# Board.net
KiCad netlist of a schematic drawn in Altium Designer
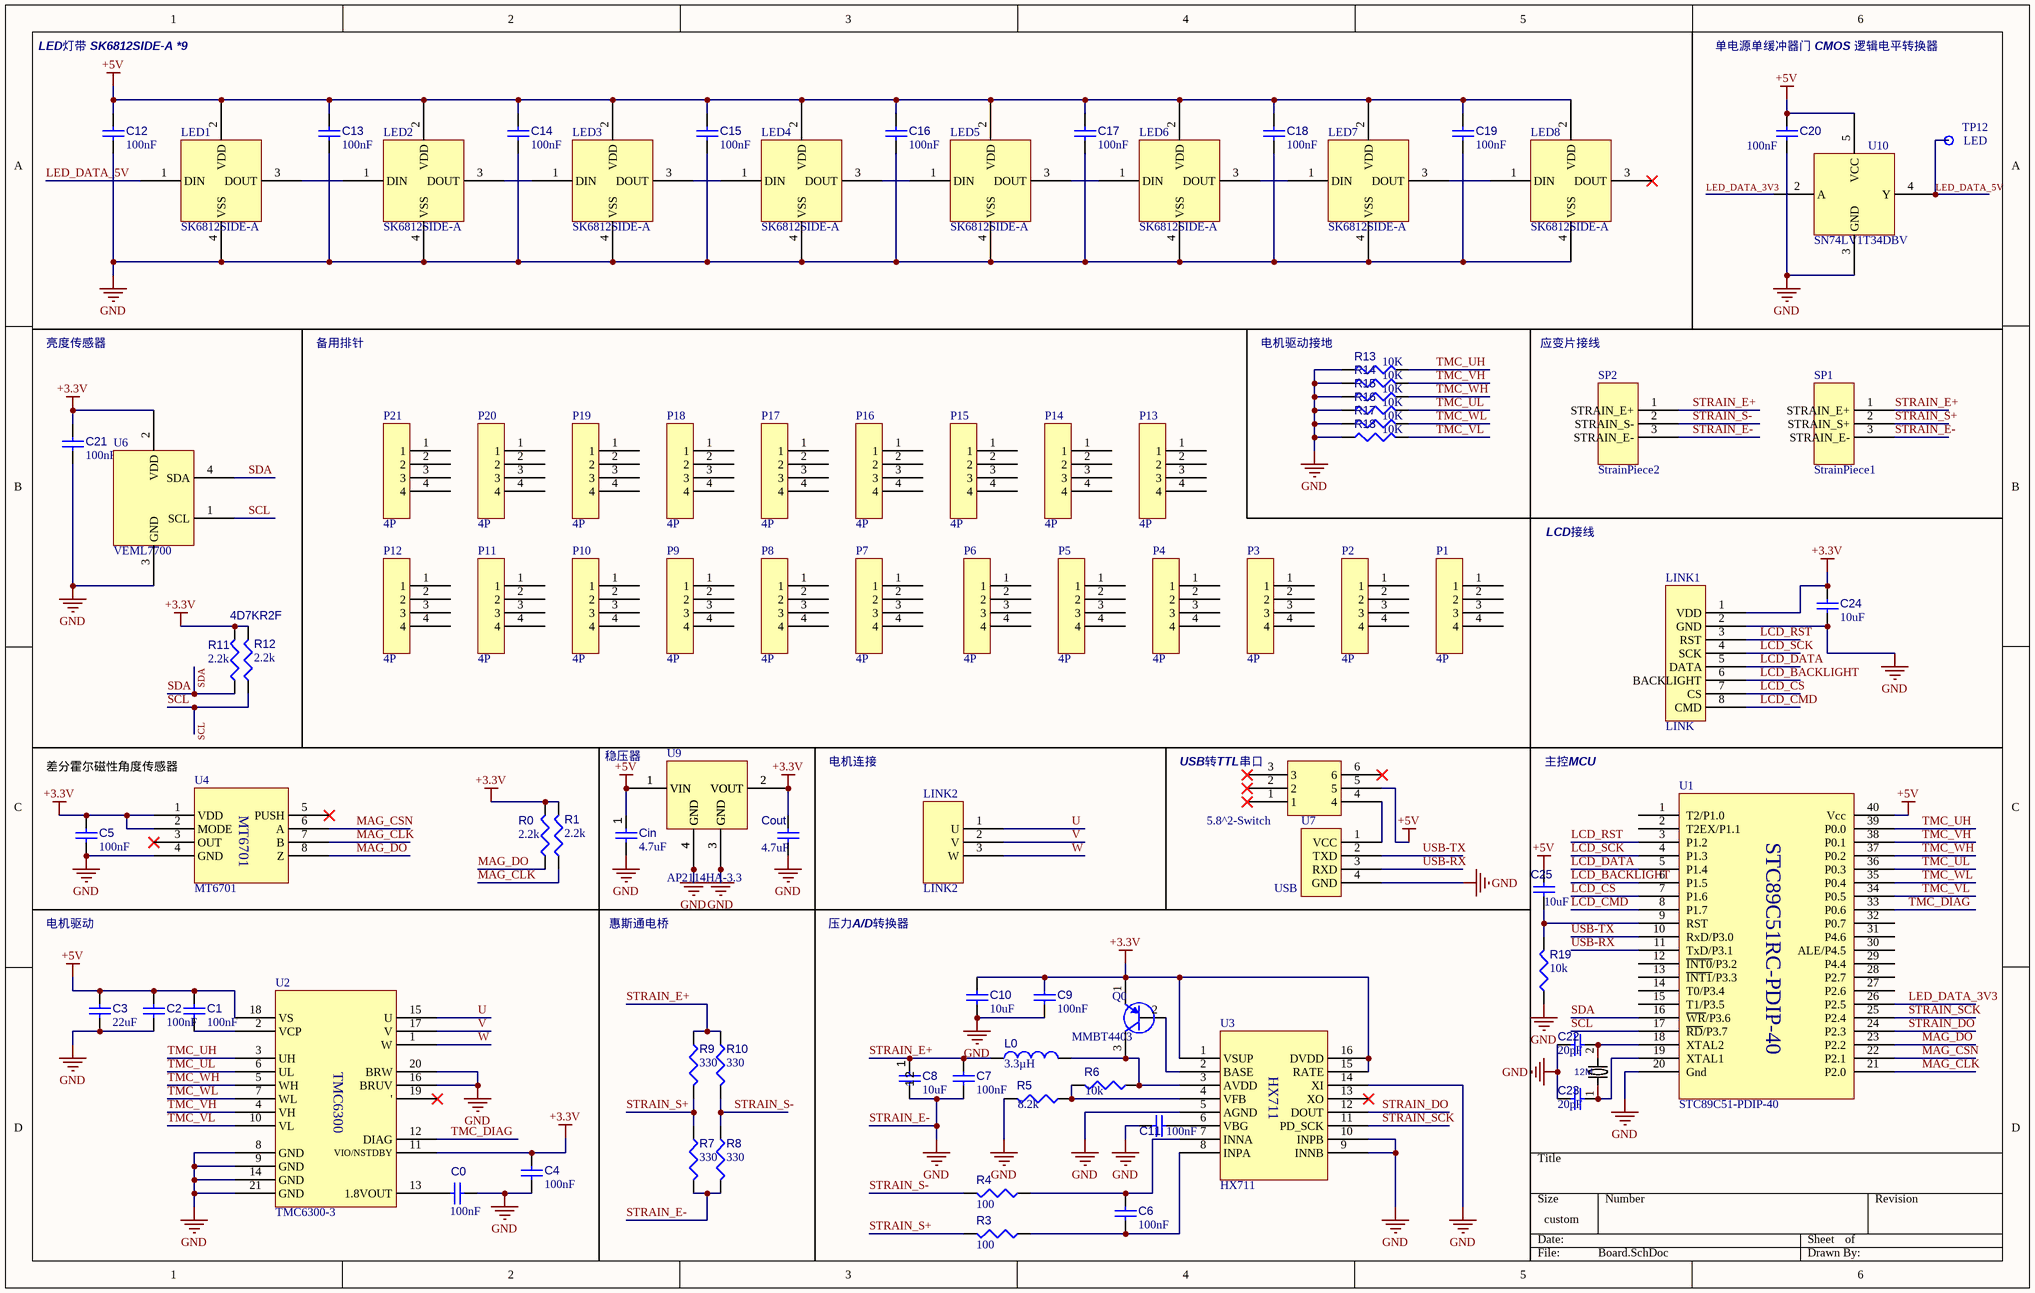
[diagram p0: Board.SchDoc]

(export (version "E")
  (design (tool "Eeschema 10.0.6"))
  (components
    (comp (ref "C0")
      (value "100nF")
      (footprint "0805贴片电容")
      (description "Chip Capacitor, 0.1 uF, +/- 5%, 16 V, 0402 (1005 Metric)")
      (fields (field (name "TOLERANCE") "5%") (field (name "Comment") "Capacitor 0.1 uF +/- 5% 16 V 0402"))
      (libsource (lib "IC") (part "CAP-NP-2"))
    )
    (comp (ref "C1")
      (value "100nF")
      (footprint "0805贴片电容")
      (description "Chip Capacitor, 0.1 uF, +/- 5%, 16 V, 0402 (1005 Metric)")
      (fields (field (name "TOLERANCE") "5%") (field (name "Comment") "Capacitor 0.1 uF +/- 5% 16 V 0402"))
      (libsource (lib "IC") (part "CAP-NP-2"))
    )
    (comp (ref "C2")
      (value "100nF")
      (footprint "0805贴片电容")
      (description "Chip Capacitor, 0.1 uF, +/- 5%, 16 V, 0402 (1005 Metric)")
      (fields (field (name "TOLERANCE") "5%") (field (name "Comment") "Capacitor 0.1 uF +/- 5% 16 V 0402"))
      (libsource (lib "IC") (part "CAP-NP-2"))
    )
    (comp (ref "C3")
      (value "22uF")
      (footprint "0805贴片电容")
      (description "Chip Capacitor, 0.1 uF, +/- 5%, 16 V, 0402 (1005 Metric)")
      (fields (field (name "TOLERANCE") "5%") (field (name "Comment") "Capacitor 0.1 uF +/- 5% 16 V 0402"))
      (libsource (lib "IC") (part "CAP-NP-2"))
    )
    (comp (ref "C4")
      (value "100nF")
      (footprint "0805贴片电容")
      (description "Chip Capacitor, 0.1 uF, +/- 5%, 16 V, 0402 (1005 Metric)")
      (fields (field (name "TOLERANCE") "5%") (field (name "Comment") "Capacitor 0.1 uF +/- 5% 16 V 0402"))
      (libsource (lib "IC") (part "CAP-NP-2"))
    )
    (comp (ref "C5")
      (value "100nF")
      (footprint "0805贴片电容")
      (description "Chip Capacitor, 0.1 uF, +/- 5%, 16 V, 0402 (1005 Metric)")
      (fields (field (name "TOLERANCE") "5%") (field (name "Comment") "Capacitor 0.1 uF +/- 5% 16 V 0402"))
      (libsource (lib "IC") (part "CAP-NP-2"))
    )
    (comp (ref "C6")
      (value "100nF")
      (footprint "0805贴片电容")
      (description "Chip Capacitor, 0.1 uF, +/- 5%, 16 V, 0402 (1005 Metric)")
      (fields (field (name "TOLERANCE") "5%") (field (name "Comment") "Capacitor 0.1 uF +/- 5% 16 V 0402"))
      (libsource (lib "IC") (part "CAP-NP-2"))
    )
    (comp (ref "C7")
      (value "100nF")
      (footprint "0805贴片电容")
      (description "Chip Capacitor, 0.1 uF, +/- 5%, 16 V, 0402 (1005 Metric)")
      (fields (field (name "TOLERANCE") "5%") (field (name "Comment") "Capacitor 0.1 uF +/- 5% 16 V 0402"))
      (libsource (lib "IC") (part "CAP-NP-2"))
    )
    (comp (ref "C8")
      (value "10uF")
      (footprint "0805贴片电容")
      (description "Chip Capacitor, 0.1 uF, +/- 5%, 16 V, 0402 (1005 Metric)")
      (fields (field (name "TOLERANCE") "5%") (field (name "Comment") "Capacitor 0.1 uF +/- 5% 16 V 0402"))
      (libsource (lib "") (part "CAP-NP-2_2"))
    )
    (comp (ref "C9")
      (value "100nF")
      (footprint "0805贴片电容")
      (description "Chip Capacitor, 0.1 uF, +/- 5%, 16 V, 0402 (1005 Metric)")
      (fields (field (name "TOLERANCE") "5%") (field (name "Comment") "Capacitor 0.1 uF +/- 5% 16 V 0402"))
      (libsource (lib "IC") (part "CAP-NP-2"))
    )
    (comp (ref "C10")
      (value "10uF")
      (footprint "0805贴片电容")
      (description "Chip Capacitor, 0.1 uF, +/- 5%, 16 V, 0402 (1005 Metric)")
      (fields (field (name "TOLERANCE") "5%") (field (name "Comment") "Capacitor 0.1 uF +/- 5% 16 V 0402"))
      (libsource (lib "IC") (part "CAP-NP-2"))
    )
    (comp (ref "C11")
      (value "100nF")
      (footprint "0805贴片电容")
      (description "Chip Capacitor, 0.1 uF, +/- 5%, 16 V, 0402 (1005 Metric)")
      (fields (field (name "TOLERANCE") "5%") (field (name "Comment") "Capacitor 0.1 uF +/- 5% 16 V 0402"))
      (libsource (lib "IC") (part "CAP-NP-2"))
    )
    (comp (ref "C12")
      (value "100nF")
      (footprint "0805贴片电容")
      (description "Chip Capacitor, 0.1 uF, +/- 5%, 16 V, 0402 (1005 Metric)")
      (fields (field (name "TOLERANCE") "5%") (field (name "Comment") "Capacitor 0.1 uF +/- 5% 16 V 0402"))
      (libsource (lib "IC") (part "CAP-NP-2"))
    )
    (comp (ref "C13")
      (value "100nF")
      (footprint "0805贴片电容")
      (description "Chip Capacitor, 0.1 uF, +/- 5%, 16 V, 0402 (1005 Metric)")
      (fields (field (name "TOLERANCE") "5%") (field (name "Comment") "Capacitor 0.1 uF +/- 5% 16 V 0402"))
      (libsource (lib "IC") (part "CAP-NP-2"))
    )
    (comp (ref "C14")
      (value "100nF")
      (footprint "0805贴片电容")
      (description "Chip Capacitor, 0.1 uF, +/- 5%, 16 V, 0402 (1005 Metric)")
      (fields (field (name "TOLERANCE") "5%") (field (name "Comment") "Capacitor 0.1 uF +/- 5% 16 V 0402"))
      (libsource (lib "IC") (part "CAP-NP-2"))
    )
    (comp (ref "C15")
      (value "100nF")
      (footprint "0805贴片电容")
      (description "Chip Capacitor, 0.1 uF, +/- 5%, 16 V, 0402 (1005 Metric)")
      (fields (field (name "TOLERANCE") "5%") (field (name "Comment") "Capacitor 0.1 uF +/- 5% 16 V 0402"))
      (libsource (lib "IC") (part "CAP-NP-2"))
    )
    (comp (ref "C16")
      (value "100nF")
      (footprint "0805贴片电容")
      (description "Chip Capacitor, 0.1 uF, +/- 5%, 16 V, 0402 (1005 Metric)")
      (fields (field (name "TOLERANCE") "5%") (field (name "Comment") "Capacitor 0.1 uF +/- 5% 16 V 0402"))
      (libsource (lib "IC") (part "CAP-NP-2"))
    )
    (comp (ref "C17")
      (value "100nF")
      (footprint "0805贴片电容")
      (description "Chip Capacitor, 0.1 uF, +/- 5%, 16 V, 0402 (1005 Metric)")
      (fields (field (name "TOLERANCE") "5%") (field (name "Comment") "Capacitor 0.1 uF +/- 5% 16 V 0402"))
      (libsource (lib "IC") (part "CAP-NP-2"))
    )
    (comp (ref "C18")
      (value "100nF")
      (footprint "0805贴片电容")
      (description "Chip Capacitor, 0.1 uF, +/- 5%, 16 V, 0402 (1005 Metric)")
      (fields (field (name "TOLERANCE") "5%") (field (name "Comment") "Capacitor 0.1 uF +/- 5% 16 V 0402"))
      (libsource (lib "IC") (part "CAP-NP-2"))
    )
    (comp (ref "C19")
      (value "100nF")
      (footprint "0805贴片电容")
      (description "Chip Capacitor, 0.1 uF, +/- 5%, 16 V, 0402 (1005 Metric)")
      (fields (field (name "TOLERANCE") "5%") (field (name "Comment") "Capacitor 0.1 uF +/- 5% 16 V 0402"))
      (libsource (lib "IC") (part "CAP-NP-2"))
    )
    (comp (ref "C20")
      (value "100nF")
      (footprint "0805贴片电容")
      (description "Chip Capacitor, 0.1 uF, +/- 5%, 16 V, 0402 (1005 Metric)")
      (fields (field (name "TOLERANCE") "5%") (field (name "Comment") "Capacitor 0.1 uF +/- 5% 16 V 0402"))
      (libsource (lib "IC") (part "CAP-NP-2"))
    )
    (comp (ref "C21")
      (value "100nF")
      (footprint "0805贴片电容")
      (description "Chip Capacitor, 0.1 uF, +/- 5%, 16 V, 0402 (1005 Metric)")
      (fields (field (name "TOLERANCE") "5%") (field (name "Comment") "Capacitor 0.1 uF +/- 5% 16 V 0402"))
      (libsource (lib "IC") (part "CAP-NP-2"))
    )
    (comp (ref "C22")
      (value "20pF")
      (footprint "0805贴片电容")
      (description "Chip Capacitor, 0.1 uF, +/- 5%, 16 V, 0402 (1005 Metric)")
      (fields (field (name "TOLERANCE") "5%") (field (name "Comment") "Capacitor 0.1 uF +/- 5% 16 V 0402"))
      (libsource (lib "IC") (part "CAP-NP-2"))
    )
    (comp (ref "C23")
      (value "20pF")
      (footprint "0805贴片电容")
      (description "Chip Capacitor, 0.1 uF, +/- 5%, 16 V, 0402 (1005 Metric)")
      (fields (field (name "TOLERANCE") "5%") (field (name "Comment") "Capacitor 0.1 uF +/- 5% 16 V 0402"))
      (libsource (lib "IC") (part "CAP-NP-2"))
    )
    (comp (ref "C24")
      (value "10uF")
      (footprint "0805贴片电容")
      (description "Chip Capacitor, 0.1 uF, +/- 5%, 16 V, 0402 (1005 Metric)")
      (fields (field (name "TOLERANCE") "5%") (field (name "Comment") "Capacitor 0.1 uF +/- 5% 16 V 0402"))
      (libsource (lib "IC") (part "CAP-NP-2"))
    )
    (comp (ref "C25")
      (value "10uF")
      (footprint "0805贴片电容")
      (description "Chip Capacitor, 0.1 uF, +/- 5%, 16 V, 0402 (1005 Metric)")
      (fields (field (name "TOLERANCE") "5%") (field (name "Comment") "Capacitor 0.1 uF +/- 5% 16 V 0402"))
      (libsource (lib "IC") (part "CAP-NP-2"))
    )
    (comp (ref "Cin")
      (value "4.7uF")
      (footprint "0805贴片电容")
      (description "Chip Capacitor, 0.1 uF, +/- 5%, 16 V, 0402 (1005 Metric)")
      (fields (field (name "TOLERANCE") "5%") (field (name "Comment") "Capacitor 0.1 uF +/- 5% 16 V 0402"))
      (libsource (lib "") (part "CAP-NP-2_1"))
    )
    (comp (ref "Cout")
      (value "4.7uF")
      (footprint "0805贴片电容")
      (description "Chip Capacitor, 0.1 uF, +/- 5%, 16 V, 0402 (1005 Metric)")
      (fields (field (name "TOLERANCE") "5%") (field (name "Comment") "Capacitor 0.1 uF +/- 5% 16 V 0402"))
      (libsource (lib "IC") (part "CAP-NP-2"))
    )
    (comp (ref "L0")
      (value "3.3µH")
      (footprint "0805贴片电容")
      (description "Chip Inductor, 1 uH, +/- 20%, 1 MHz, -55 to 125 degC, 1008 (2520 Metric), RoHS, Tape and Reel")
      (fields (field (name "TOLERANCE") "20%") (field (name "MANUFACTURER") "Murata"))
      (libsource (lib "MainBoard") (part "IND-2"))
    )
    (comp (ref "LED1")
      (value "SK6812SIDE-A")
      (footprint "FZ-SK6812SIDE-A")
      (libsource (lib "DigiPCBA Workspace") (part "SK6812SIDE-A"))
    )
    (comp (ref "LED2")
      (value "SK6812SIDE-A")
      (footprint "FZ-SK6812SIDE-A")
      (libsource (lib "DigiPCBA Workspace") (part "SK6812SIDE-A"))
    )
    (comp (ref "LED3")
      (value "SK6812SIDE-A")
      (footprint "FZ-SK6812SIDE-A")
      (libsource (lib "DigiPCBA Workspace") (part "SK6812SIDE-A"))
    )
    (comp (ref "LED4")
      (value "SK6812SIDE-A")
      (footprint "FZ-SK6812SIDE-A")
      (libsource (lib "DigiPCBA Workspace") (part "SK6812SIDE-A"))
    )
    (comp (ref "LED5")
      (value "SK6812SIDE-A")
      (footprint "FZ-SK6812SIDE-A")
      (libsource (lib "DigiPCBA Workspace") (part "SK6812SIDE-A"))
    )
    (comp (ref "LED6")
      (value "SK6812SIDE-A")
      (footprint "FZ-SK6812SIDE-A")
      (libsource (lib "DigiPCBA Workspace") (part "SK6812SIDE-A"))
    )
    (comp (ref "LED7")
      (value "SK6812SIDE-A")
      (footprint "FZ-SK6812SIDE-A")
      (libsource (lib "DigiPCBA Workspace") (part "SK6812SIDE-A"))
    )
    (comp (ref "LED8")
      (value "SK6812SIDE-A")
      (footprint "FZ-SK6812SIDE-A")
      (libsource (lib "DigiPCBA Workspace") (part "SK6812SIDE-A"))
    )
    (comp (ref "LINK1")
      (value "LINK")
      (footprint "LINK")
      (libsource (lib "DigiPCBA Workspace") (part "LINK"))
    )
    (comp (ref "LINK2")
      (value "LINK2")
      (footprint "LINK2")
      (libsource (lib "DigiPCBA Workspace") (part "LINK2"))
    )
    (comp (ref "P1") (value "4P") (footprint "2.54管脚") (libsource (lib "DigiPCBA Workspace") (part "4P")))
    (comp (ref "P2") (value "4P") (footprint "2.54管脚") (libsource (lib "DigiPCBA Workspace") (part "4P")))
    (comp (ref "P3") (value "4P") (footprint "2.54管脚") (libsource (lib "DigiPCBA Workspace") (part "4P")))
    (comp (ref "P4") (value "4P") (footprint "2.54管脚") (libsource (lib "DigiPCBA Workspace") (part "4P")))
    (comp (ref "P5") (value "4P") (footprint "2.54管脚") (libsource (lib "DigiPCBA Workspace") (part "4P")))
    (comp (ref "P6") (value "4P") (footprint "2.54管脚") (libsource (lib "DigiPCBA Workspace") (part "4P")))
    (comp (ref "P7") (value "4P") (footprint "2.54管脚") (libsource (lib "DigiPCBA Workspace") (part "4P")))
    (comp (ref "P8") (value "4P") (footprint "2.54管脚") (libsource (lib "DigiPCBA Workspace") (part "4P")))
    (comp (ref "P9") (value "4P") (footprint "2.54管脚") (libsource (lib "DigiPCBA Workspace") (part "4P")))
    (comp (ref "P10") (value "4P") (footprint "2.54管脚") (libsource (lib "DigiPCBA Workspace") (part "4P")))
    (comp (ref "P11") (value "4P") (footprint "2.54管脚") (libsource (lib "DigiPCBA Workspace") (part "4P")))
    (comp (ref "P12") (value "4P") (footprint "2.54管脚") (libsource (lib "DigiPCBA Workspace") (part "4P")))
    (comp (ref "P13") (value "4P") (footprint "2.54管脚") (libsource (lib "DigiPCBA Workspace") (part "4P")))
    (comp (ref "P14") (value "4P") (footprint "2.54管脚") (libsource (lib "DigiPCBA Workspace") (part "4P")))
    (comp (ref "P15") (value "4P") (footprint "2.54管脚") (libsource (lib "DigiPCBA Workspace") (part "4P")))
    (comp (ref "P16") (value "4P") (footprint "2.54管脚") (libsource (lib "DigiPCBA Workspace") (part "4P")))
    (comp (ref "P17") (value "4P") (footprint "2.54管脚") (libsource (lib "DigiPCBA Workspace") (part "4P")))
    (comp (ref "P18") (value "4P") (footprint "2.54管脚") (libsource (lib "DigiPCBA Workspace") (part "4P")))
    (comp (ref "P19") (value "4P") (footprint "2.54管脚") (libsource (lib "DigiPCBA Workspace") (part "4P")))
    (comp (ref "P20") (value "4P") (footprint "2.54管脚") (libsource (lib "DigiPCBA Workspace") (part "4P")))
    (comp (ref "P21") (value "4P") (footprint "2.54管脚") (libsource (lib "DigiPCBA Workspace") (part "4P")))
    (comp (ref "Q0")
      (value "MMBT4403")
      (footprint "FZ-MMBT4403")
      (fields (field (name "MANUFACTURER") "Unisonic"))
      (libsource (lib "MainBoard") (part "BJT-PNP-EBC-3"))
    )
    (comp (ref "R0")
      (value "2.2k")
      (footprint "0805贴片电容")
      (description "4K7 0.063W 1% 0402 (1005 Metric)  SMD")
      (fields (field (name "TOLERANCE") "1%") (field (name "POWER") "63mW"))
      (libsource (lib "MainBoard") (part "4D7KR2F"))
    )
    (comp (ref "R1")
      (value "2.2k")
      (footprint "0805贴片电容")
      (description "4K7 0.063W 1% 0402 (1005 Metric)  SMD")
      (fields (field (name "TOLERANCE") "1%") (field (name "POWER") "63mW"))
      (libsource (lib "MainBoard") (part "4D7KR2F"))
    )
    (comp (ref "R3")
      (value "100")
      (footprint "0805贴片电容")
      (description "4K7 0.063W 1% 0402 (1005 Metric)  SMD")
      (fields (field (name "TOLERANCE") "1%") (field (name "POWER") "63mW"))
      (libsource (lib "MainBoard") (part "4D7KR2F"))
    )
    (comp (ref "R4")
      (value "100")
      (footprint "0805贴片电容")
      (description "4K7 0.063W 1% 0402 (1005 Metric)  SMD")
      (fields (field (name "TOLERANCE") "1%") (field (name "POWER") "63mW"))
      (libsource (lib "MainBoard") (part "4D7KR2F"))
    )
    (comp (ref "R5")
      (value "8.2k")
      (footprint "0805贴片电容")
      (description "4K7 0.063W 1% 0402 (1005 Metric)  SMD")
      (fields (field (name "TOLERANCE") "1%") (field (name "POWER") "63mW"))
      (libsource (lib "MainBoard") (part "4D7KR2F"))
    )
    (comp (ref "R6")
      (value "10k")
      (footprint "0805贴片电容")
      (description "4K7 0.063W 1% 0402 (1005 Metric)  SMD")
      (fields (field (name "TOLERANCE") "1%") (field (name "POWER") "63mW"))
      (libsource (lib "MainBoard") (part "4D7KR2F"))
    )
    (comp (ref "R7")
      (value "330")
      (footprint "0805贴片电容")
      (description "4K7 0.063W 1% 0402 (1005 Metric)  SMD")
      (fields (field (name "TOLERANCE") "1%") (field (name "POWER") "63mW"))
      (libsource (lib "MainBoard") (part "4D7KR2F"))
    )
    (comp (ref "R8")
      (value "330")
      (footprint "0805贴片电容")
      (description "4K7 0.063W 1% 0402 (1005 Metric)  SMD")
      (fields (field (name "TOLERANCE") "1%") (field (name "POWER") "63mW"))
      (libsource (lib "MainBoard") (part "4D7KR2F"))
    )
    (comp (ref "R9")
      (value "330")
      (footprint "0805贴片电容")
      (description "4K7 0.063W 1% 0402 (1005 Metric)  SMD")
      (fields (field (name "TOLERANCE") "1%") (field (name "POWER") "63mW"))
      (libsource (lib "MainBoard") (part "4D7KR2F"))
    )
    (comp (ref "R10")
      (value "330")
      (footprint "0805贴片电容")
      (description "4K7 0.063W 1% 0402 (1005 Metric)  SMD")
      (fields (field (name "TOLERANCE") "1%") (field (name "POWER") "63mW"))
      (libsource (lib "MainBoard") (part "4D7KR2F"))
    )
    (comp (ref "R11")
      (value "4D7KR2F")
      (footprint "0805贴片电容")
      (fields
        (field (name "TOLERANCE") "1%")
        (field (name "POWER") "63mW")
        (field (name "ALTIUM_VALUE") "2.2k")
      )
      (libsource (lib "MainBoard") (part "4D7KR2F"))
    )
    (comp (ref "R12")
      (value "2.2k")
      (footprint "0805贴片电容")
      (description "4K7 0.063W 1% 0402 (1005 Metric)  SMD")
      (fields (field (name "TOLERANCE") "1%") (field (name "POWER") "63mW"))
      (libsource (lib "MainBoard") (part "4D7KR2F"))
    )
    (comp (ref "R13")
      (value "10K")
      (footprint "0805贴片电容")
      (description "4K7 0.063W 1% 0402 (1005 Metric)  SMD")
      (fields (field (name "TOLERANCE") "1%") (field (name "POWER") "63mW"))
      (libsource (lib "MainBoard") (part "4D7KR2F"))
    )
    (comp (ref "R14")
      (value "10K")
      (footprint "0805贴片电容")
      (description "4K7 0.063W 1% 0402 (1005 Metric)  SMD")
      (fields (field (name "TOLERANCE") "1%") (field (name "POWER") "63mW"))
      (libsource (lib "MainBoard") (part "4D7KR2F"))
    )
    (comp (ref "R15")
      (value "10K")
      (footprint "0805贴片电容")
      (description "4K7 0.063W 1% 0402 (1005 Metric)  SMD")
      (fields (field (name "TOLERANCE") "1%") (field (name "POWER") "63mW"))
      (libsource (lib "MainBoard") (part "4D7KR2F"))
    )
    (comp (ref "R16")
      (value "10K")
      (footprint "0805贴片电容")
      (description "4K7 0.063W 1% 0402 (1005 Metric)  SMD")
      (fields (field (name "TOLERANCE") "1%") (field (name "POWER") "63mW"))
      (libsource (lib "MainBoard") (part "4D7KR2F"))
    )
    (comp (ref "R17")
      (value "10K")
      (footprint "0805贴片电容")
      (description "4K7 0.063W 1% 0402 (1005 Metric)  SMD")
      (fields (field (name "TOLERANCE") "1%") (field (name "POWER") "63mW"))
      (libsource (lib "MainBoard") (part "4D7KR2F"))
    )
    (comp (ref "R18")
      (value "10K")
      (footprint "0805贴片电容")
      (description "4K7 0.063W 1% 0402 (1005 Metric)  SMD")
      (fields (field (name "TOLERANCE") "1%") (field (name "POWER") "63mW"))
      (libsource (lib "MainBoard") (part "4D7KR2F"))
    )
    (comp (ref "R19")
      (value "10k")
      (footprint "0805贴片电容")
      (description "4K7 0.063W 1% 0402 (1005 Metric)  SMD")
      (fields (field (name "TOLERANCE") "1%") (field (name "POWER") "63mW"))
      (libsource (lib "MainBoard") (part "4D7KR2F"))
    )
    (comp (ref "S1")
      (value "5.8^2-Switch")
      (footprint "FZ-Switch")
      (fields (field (name "DESIGNER") "U?"))
      (libsource (lib "DigiPCBA Workspace") (part "5.8^2-Switch"))
    )
    (comp (ref "SP1")
      (value "StrainPiece1")
      (footprint "LINK2")
      (libsource (lib "DigiPCBA Workspace") (part "StrainPiece1"))
    )
    (comp (ref "SP2")
      (value "StrainPiece2")
      (footprint "LINK2")
      (libsource (lib "DigiPCBA Workspace") (part "StrainPiece2"))
    )
    (comp (ref "U1")
      (value "STC89C51-PDIP-40")
      (footprint "封装.STC89C51-PDIP-40")
      (description "主控MCU")
      (libsource (lib "DigiPCBA Workspace") (part "STC89C51-PDIP-40"))
    )
    (comp (ref "U2")
      (value "TMC6300-3")
      (footprint "封装.TMC6300")
      (libsource (lib "DigiPCBA Workspace") (part "TMC6300-3"))
    )
    (comp (ref "U3")
      (value "HX711")
      (footprint "封装.HX711")
      (description "压力模数转换器")
      (libsource (lib "DigiPCBA Workspace") (part "HX711"))
    )
    (comp (ref "U4")
      (value "MT6701")
      (footprint "封装.MT6701")
      (description "霍尔传感器")
      (libsource (lib "DigiPCBA Workspace") (part "MT6701"))
    )
    (comp (ref "U6")
      (value "VEML7700")
      (footprint "封装.VEML7700")
      (description "感光想读传感器")
      (libsource (lib "DigiPCBA Workspace") (part "VEML7700"))
    )
    (comp (ref "U7") (value "USB") (footprint "2.54管脚") (libsource (lib "MainBoard") (part "USB")))
    (comp (ref "U9")
      (value "AP2114HA-3.3")
      (footprint "封装.AP2114HA-3.3TRG1")
      (description "电压控制器")
      (libsource (lib "DigiPCBA Workspace") (part "AP2114HA-3.3"))
    )
    (comp (ref "U10")
      (value "SN74LV1T34DBV")
      (footprint "封装.SN74LV1T34DBVR")
      (description "电流放大器")
      (libsource (lib "DigiPCBA Workspace") (part "SN74LV1T34DBV"))
    )
    (comp (ref "X1")
      (value "9C12000002")
      (footprint "HC-49S_L11.4-W4.8")
      (fields (field (name "MANUFACTURER") "TXC(晶技)"))
      (libsource (lib "DigiPCBA Workspace") (part "9C12000002"))
    )
  )
  (nets
    (net (code "1") (name "+3.3V") (class "Default")
      (node (ref "C10") (pin "1") (pinfunction "1_1") (pintype "passive"))
      (node (ref "C21") (pin "1") (pinfunction "1_1") (pintype "passive"))
      (node (ref "C24") (pin "2") (pinfunction "2_2") (pintype "passive"))
      (node (ref "C4") (pin "1") (pinfunction "1_1") (pintype "passive"))
      (node (ref "C5") (pin "1") (pinfunction "1_1") (pintype "passive"))
      (node (ref "C9") (pin "1") (pinfunction "1_1") (pintype "passive"))
      (node (ref "Cout") (pin "1") (pinfunction "1_1") (pintype "passive"))
      (node (ref "LINK1") (pin "1") (pinfunction "VDD_1") (pintype "open_collector"))
      (node (ref "Q0") (pin "1") (pinfunction "E_1") (pintype "passive"))
      (node (ref "R0") (pin "2") (pinfunction "2_2") (pintype "passive"))
      (node (ref "R1") (pin "2") (pinfunction "2_2") (pintype "passive"))
      (node (ref "R11") (pin "2") (pinfunction "2_2") (pintype "passive"))
      (node (ref "R12") (pin "2") (pinfunction "2_2") (pintype "passive"))
      (node (ref "U2") (pin "11") (pinfunction "VIO/NSTDBY_11") (pintype "open_collector"))
      (node (ref "U3") (pin "1") (pinfunction "VSUP_1") (pintype "open_collector"))
      (node (ref "U3") (pin "15") (pinfunction "RATE_15") (pintype "open_collector"))
      (node (ref "U3") (pin "16") (pinfunction "DVDD_16") (pintype "open_collector"))
      (node (ref "U4") (pin "1") (pinfunction "VDD_1") (pintype "open_collector"))
      (node (ref "U4") (pin "2") (pinfunction "MODE_2") (pintype "open_collector"))
      (node (ref "U6") (pin "2") (pinfunction "VDD_2") (pintype "open_collector"))
      (node (ref "U9") (pin "2") (pinfunction "VOUT_2") (pintype "open_collector"))
    )
    (net (code "2") (name "+5V") (class "Default")
      (node (ref "C1") (pin "1") (pinfunction "1_1") (pintype "passive"))
      (node (ref "C12") (pin "1") (pinfunction "1_1") (pintype "passive"))
      (node (ref "C13") (pin "1") (pinfunction "1_1") (pintype "passive"))
      (node (ref "C14") (pin "1") (pinfunction "1_1") (pintype "passive"))
      (node (ref "C15") (pin "1") (pinfunction "1_1") (pintype "passive"))
      (node (ref "C16") (pin "1") (pinfunction "1_1") (pintype "passive"))
      (node (ref "C17") (pin "1") (pinfunction "1_1") (pintype "passive"))
      (node (ref "C18") (pin "1") (pinfunction "1_1") (pintype "passive"))
      (node (ref "C19") (pin "1") (pinfunction "1_1") (pintype "passive"))
      (node (ref "C2") (pin "1") (pinfunction "1_1") (pintype "passive"))
      (node (ref "C20") (pin "1") (pinfunction "1_1") (pintype "passive"))
      (node (ref "C25") (pin "1") (pinfunction "1_1") (pintype "passive"))
      (node (ref "C3") (pin "1") (pinfunction "1_1") (pintype "passive"))
      (node (ref "Cin") (pin "1") (pinfunction "1_1") (pintype "passive"))
      (node (ref "LED1") (pin "2") (pinfunction "VDD_2") (pintype "open_collector"))
      (node (ref "LED2") (pin "2") (pinfunction "VDD_2") (pintype "open_collector"))
      (node (ref "LED3") (pin "2") (pinfunction "VDD_2") (pintype "open_collector"))
      (node (ref "LED4") (pin "2") (pinfunction "VDD_2") (pintype "open_collector"))
      (node (ref "LED5") (pin "2") (pinfunction "VDD_2") (pintype "open_collector"))
      (node (ref "LED6") (pin "2") (pinfunction "VDD_2") (pintype "open_collector"))
      (node (ref "LED7") (pin "2") (pinfunction "VDD_2") (pintype "open_collector"))
      (node (ref "LED8") (pin "2") (pinfunction "VDD_2") (pintype "open_collector"))
      (node (ref "S1") (pin "5") (pinfunction "5_5") (pintype "open_collector"))
      (node (ref "U1") (pin "40") (pinfunction "Vcc_40") (pintype "open_collector"))
      (node (ref "U10") (pin "5") (pinfunction "VCC_5") (pintype "open_collector"))
      (node (ref "U2") (pin "18") (pinfunction "VS_18") (pintype "open_collector"))
      (node (ref "U9") (pin "1") (pinfunction "VIN_1") (pintype "open_collector"))
    )
    (net (code "3") (name "/LCD_BACKLIGHT") (class "Default")
      (node (ref "LINK1") (pin "6") (pinfunction "BACKLIGHT_6") (pintype "open_collector"))
      (node (ref "U1") (pin "6") (pinfunction "P1.5_6") (pintype "open_collector"))
    )
    (net (code "4") (name "/LCD_CMD") (class "Default")
      (node (ref "LINK1") (pin "8") (pinfunction "CMD_8") (pintype "open_collector"))
      (node (ref "U1") (pin "8") (pinfunction "P1.7_8") (pintype "open_collector"))
    )
    (net (code "5") (name "/LCD_CS") (class "Default")
      (node (ref "LINK1") (pin "7") (pinfunction "CS_7") (pintype "open_collector"))
      (node (ref "U1") (pin "7") (pinfunction "P1.6_7") (pintype "open_collector"))
    )
    (net (code "6") (name "/LCD_DATA") (class "Default")
      (node (ref "LINK1") (pin "5") (pinfunction "DATA_5") (pintype "open_collector"))
      (node (ref "U1") (pin "5") (pinfunction "P1.4_5") (pintype "open_collector"))
    )
    (net (code "7") (name "/LCD_RST") (class "Default")
      (node (ref "LINK1") (pin "3") (pinfunction "RST_3") (pintype "open_collector"))
      (node (ref "U1") (pin "3") (pinfunction "P1.2_3") (pintype "open_collector"))
    )
    (net (code "8") (name "/LCD_SCK") (class "Default")
      (node (ref "LINK1") (pin "4") (pinfunction "SCK_4") (pintype "open_collector"))
      (node (ref "U1") (pin "4") (pinfunction "P1.3_4") (pintype "open_collector"))
    )
    (net (code "9") (name "/LED_DATA_3V3") (class "Default")
      (node (ref "U1") (pin "26") (pinfunction "P2.5_26") (pintype "open_collector"))
      (node (ref "U10") (pin "2") (pinfunction "A_2") (pintype "open_collector"))
    )
    (net (code "10") (name "/LED_DATA_5V") (class "Default")
      (node (ref "LED1") (pin "1") (pinfunction "DIN_1") (pintype "open_collector"))
      (node (ref "U10") (pin "4") (pinfunction "Y_4") (pintype "open_collector"))
    )
    (net (code "11") (name "/MAG_CLK") (class "Default")
      (node (ref "R1") (pin "1") (pinfunction "1_1") (pintype "passive"))
      (node (ref "U1") (pin "21") (pinfunction "P2.0_21") (pintype "open_collector"))
      (node (ref "U4") (pin "7") (pinfunction "B_7") (pintype "open_collector"))
    )
    (net (code "12") (name "/MAG_CSN") (class "Default")
      (node (ref "U1") (pin "22") (pinfunction "P2.1_22") (pintype "open_collector"))
      (node (ref "U4") (pin "6") (pinfunction "A_6") (pintype "open_collector"))
    )
    (net (code "13") (name "/MAG_DO") (class "Default")
      (node (ref "R0") (pin "1") (pinfunction "1_1") (pintype "passive"))
      (node (ref "U1") (pin "23") (pinfunction "P2.2_23") (pintype "open_collector"))
      (node (ref "U4") (pin "8") (pinfunction "Z_8") (pintype "open_collector"))
    )
    (net (code "14") (name "/SCL") (class "Default")
      (node (ref "R12") (pin "1") (pinfunction "1_1") (pintype "passive"))
      (node (ref "U1") (pin "17") (pinfunction "~{RD}/P3.7_17") (pintype "open_collector"))
      (node (ref "U6") (pin "1") (pinfunction "SCL_1") (pintype "open_collector"))
    )
    (net (code "15") (name "/SDA") (class "Default")
      (node (ref "R11") (pin "1") (pinfunction "1_1") (pintype "passive"))
      (node (ref "U1") (pin "16") (pinfunction "~{WR}/P3.6_16") (pintype "open_collector"))
      (node (ref "U6") (pin "4") (pinfunction "SDA_4") (pintype "open_collector"))
    )
    (net (code "16") (name "/STRAIN_DO") (class "Default")
      (node (ref "U1") (pin "24") (pinfunction "P2.3_24") (pintype "open_collector"))
      (node (ref "U3") (pin "12") (pinfunction "DOUT_12") (pintype "open_collector"))
    )
    (net (code "17") (name "/STRAIN_E+") (class "Default")
      (node (ref "C7") (pin "1") (pinfunction "1_1") (pintype "passive"))
      (node (ref "C8") (pin "1") (pinfunction "1_1") (pintype "passive"))
      (node (ref "L0") (pin "1") (pinfunction "1_1") (pintype "passive"))
      (node (ref "R10") (pin "1") (pinfunction "1_1") (pintype "passive"))
      (node (ref "R9") (pin "1") (pinfunction "1_1") (pintype "passive"))
      (node (ref "SP1") (pin "1") (pinfunction "STRAIN_E+_1") (pintype "open_collector"))
      (node (ref "SP2") (pin "1") (pinfunction "STRAIN_E+_1") (pintype "open_collector"))
    )
    (net (code "18") (name "/STRAIN_S+") (class "Default")
      (node (ref "R3") (pin "2") (pinfunction "2_2") (pintype "passive"))
      (node (ref "R7") (pin "1") (pinfunction "1_1") (pintype "passive"))
      (node (ref "R9") (pin "2") (pinfunction "2_2") (pintype "passive"))
      (node (ref "SP1") (pin "2") (pinfunction "STRAIN_S+_2") (pintype "open_collector"))
    )
    (net (code "19") (name "/STRAIN_S-") (class "Default")
      (node (ref "R10") (pin "2") (pinfunction "2_2") (pintype "passive"))
      (node (ref "R4") (pin "2") (pinfunction "2_2") (pintype "passive"))
      (node (ref "R8") (pin "1") (pinfunction "1_1") (pintype "passive"))
      (node (ref "SP2") (pin "2") (pinfunction "STRAIN_S-_2") (pintype "open_collector"))
    )
    (net (code "20") (name "/STRAIN_SCK") (class "Default")
      (node (ref "U1") (pin "25") (pinfunction "P2.4_25") (pintype "open_collector"))
      (node (ref "U3") (pin "11") (pinfunction "PD_SCK_11") (pintype "open_collector"))
    )
    (net (code "21") (name "/TMC_DIAG") (class "Default")
      (node (ref "U1") (pin "33") (pinfunction "P0.6_33") (pintype "open_collector"))
      (node (ref "U2") (pin "12") (pinfunction "DIAG_12") (pintype "open_collector"))
    )
    (net (code "22") (name "/TMC_UH") (class "Default")
      (node (ref "R13") (pin "2") (pinfunction "2_2") (pintype "passive"))
      (node (ref "U1") (pin "39") (pinfunction "P0.0_39") (pintype "open_collector"))
      (node (ref "U2") (pin "3") (pinfunction "UH_3") (pintype "open_collector"))
    )
    (net (code "23") (name "/TMC_UL") (class "Default")
      (node (ref "R16") (pin "2") (pinfunction "2_2") (pintype "passive"))
      (node (ref "U1") (pin "36") (pinfunction "P0.3_36") (pintype "open_collector"))
      (node (ref "U2") (pin "6") (pinfunction "UL_6") (pintype "open_collector"))
    )
    (net (code "24") (name "/TMC_VH") (class "Default")
      (node (ref "R14") (pin "2") (pinfunction "2_2") (pintype "passive"))
      (node (ref "U1") (pin "38") (pinfunction "P0.1_38") (pintype "open_collector"))
      (node (ref "U2") (pin "4") (pinfunction "VH_4") (pintype "open_collector"))
    )
    (net (code "25") (name "/TMC_VL") (class "Default")
      (node (ref "R18") (pin "2") (pinfunction "2_2") (pintype "passive"))
      (node (ref "U1") (pin "34") (pinfunction "P0.5_34") (pintype "open_collector"))
      (node (ref "U2") (pin "10") (pinfunction "VL_10") (pintype "open_collector"))
    )
    (net (code "26") (name "/TMC_WH") (class "Default")
      (node (ref "R15") (pin "2") (pinfunction "2_2") (pintype "passive"))
      (node (ref "U1") (pin "37") (pinfunction "P0.2_37") (pintype "open_collector"))
      (node (ref "U2") (pin "5") (pinfunction "WH_5") (pintype "open_collector"))
    )
    (net (code "27") (name "/TMC_WL") (class "Default")
      (node (ref "R17") (pin "2") (pinfunction "2_2") (pintype "passive"))
      (node (ref "U1") (pin "35") (pinfunction "P0.4_35") (pintype "open_collector"))
      (node (ref "U2") (pin "7") (pinfunction "WL_7") (pintype "open_collector"))
    )
    (net (code "28") (name "/U") (class "Default")
      (node (ref "LINK2") (pin "1") (pinfunction "U_1") (pintype "open_collector"))
      (node (ref "U2") (pin "15") (pinfunction "U_15") (pintype "open_collector"))
    )
    (net (code "29") (name "/USB-RX") (class "Default")
      (node (ref "U1") (pin "11") (pinfunction "TxD/P3.1_11") (pintype "open_collector"))
      (node (ref "U7") (pin "3") (pinfunction "RXD_3") (pintype "open_collector"))
    )
    (net (code "30") (name "/USB-TX") (class "Default")
      (node (ref "U1") (pin "10") (pinfunction "RxD/P3.0_10") (pintype "open_collector"))
      (node (ref "U7") (pin "2") (pinfunction "TXD_2") (pintype "open_collector"))
    )
    (net (code "31") (name "/V") (class "Default")
      (node (ref "LINK2") (pin "2") (pinfunction "V_2") (pintype "open_collector"))
      (node (ref "U2") (pin "17") (pinfunction "V_17") (pintype "open_collector"))
    )
    (net (code "32") (name "/W") (class "Default")
      (node (ref "LINK2") (pin "3") (pinfunction "W_3") (pintype "open_collector"))
      (node (ref "U2") (pin "1") (pinfunction "W_1") (pintype "open_collector"))
    )
    (net (code "33") (name "GND") (class "Default")
      (node (ref "C0") (pin "1") (pinfunction "1_1") (pintype "passive"))
      (node (ref "C10") (pin "2") (pinfunction "2_2") (pintype "passive"))
      (node (ref "C11") (pin "1") (pinfunction "1_1") (pintype "passive"))
      (node (ref "C12") (pin "2") (pinfunction "2_2") (pintype "passive"))
      (node (ref "C13") (pin "2") (pinfunction "2_2") (pintype "passive"))
      (node (ref "C14") (pin "2") (pinfunction "2_2") (pintype "passive"))
      (node (ref "C15") (pin "2") (pinfunction "2_2") (pintype "passive"))
      (node (ref "C16") (pin "2") (pinfunction "2_2") (pintype "passive"))
      (node (ref "C17") (pin "2") (pinfunction "2_2") (pintype "passive"))
      (node (ref "C18") (pin "2") (pinfunction "2_2") (pintype "passive"))
      (node (ref "C19") (pin "2") (pinfunction "2_2") (pintype "passive"))
      (node (ref "C2") (pin "2") (pinfunction "2_2") (pintype "passive"))
      (node (ref "C20") (pin "2") (pinfunction "2_2") (pintype "passive"))
      (node (ref "C21") (pin "2") (pinfunction "2_2") (pintype "passive"))
      (node (ref "C22") (pin "1") (pinfunction "1_1") (pintype "passive"))
      (node (ref "C23") (pin "1") (pinfunction "1_1") (pintype "passive"))
      (node (ref "C24") (pin "1") (pinfunction "1_1") (pintype "passive"))
      (node (ref "C3") (pin "2") (pinfunction "2_2") (pintype "passive"))
      (node (ref "C4") (pin "2") (pinfunction "2_2") (pintype "passive"))
      (node (ref "C5") (pin "2") (pinfunction "2_2") (pintype "passive"))
      (node (ref "C7") (pin "2") (pinfunction "2_2") (pintype "passive"))
      (node (ref "C8") (pin "2") (pinfunction "2_2") (pintype "passive"))
      (node (ref "C9") (pin "2") (pinfunction "2_2") (pintype "passive"))
      (node (ref "Cin") (pin "2") (pinfunction "2_2") (pintype "passive"))
      (node (ref "Cout") (pin "2") (pinfunction "2_2") (pintype "passive"))
      (node (ref "LED1") (pin "4") (pinfunction "VSS_4") (pintype "open_collector"))
      (node (ref "LED2") (pin "4") (pinfunction "VSS_4") (pintype "open_collector"))
      (node (ref "LED3") (pin "4") (pinfunction "VSS_4") (pintype "open_collector"))
      (node (ref "LED4") (pin "4") (pinfunction "VSS_4") (pintype "open_collector"))
      (node (ref "LED5") (pin "4") (pinfunction "VSS_4") (pintype "open_collector"))
      (node (ref "LED6") (pin "4") (pinfunction "VSS_4") (pintype "open_collector"))
      (node (ref "LED7") (pin "4") (pinfunction "VSS_4") (pintype "open_collector"))
      (node (ref "LED8") (pin "4") (pinfunction "VSS_4") (pintype "open_collector"))
      (node (ref "LINK1") (pin "2") (pinfunction "GND_2") (pintype "open_collector"))
      (node (ref "R13") (pin "1") (pinfunction "1_1") (pintype "passive"))
      (node (ref "R14") (pin "1") (pinfunction "1_1") (pintype "passive"))
      (node (ref "R15") (pin "1") (pinfunction "1_1") (pintype "passive"))
      (node (ref "R16") (pin "1") (pinfunction "1_1") (pintype "passive"))
      (node (ref "R17") (pin "1") (pinfunction "1_1") (pintype "passive"))
      (node (ref "R18") (pin "1") (pinfunction "1_1") (pintype "passive"))
      (node (ref "R19") (pin "1") (pinfunction "1_1") (pintype "passive"))
      (node (ref "R5") (pin "2") (pinfunction "2_2") (pintype "passive"))
      (node (ref "R7") (pin "2") (pinfunction "2_2") (pintype "passive"))
      (node (ref "R8") (pin "2") (pinfunction "2_2") (pintype "passive"))
      (node (ref "SP1") (pin "3") (pinfunction "STRAIN_E-_3") (pintype "open_collector"))
      (node (ref "SP2") (pin "3") (pinfunction "STRAIN_E-_3") (pintype "open_collector"))
      (node (ref "U1") (pin "20") (pinfunction "Gnd_20") (pintype "open_collector"))
      (node (ref "U10") (pin "3") (pinfunction "GND_3") (pintype "open_collector"))
      (node (ref "U2") (pin "14") (pinfunction "GND_14") (pintype "open_collector"))
      (node (ref "U2") (pin "16") (pinfunction "BRUV_16") (pintype "open_collector"))
      (node (ref "U2") (pin "20") (pinfunction "BRW_20") (pintype "open_collector"))
      (node (ref "U2") (pin "21") (pinfunction "GND_21") (pintype "open_collector"))
      (node (ref "U2") (pin "8") (pinfunction "GND_8") (pintype "open_collector"))
      (node (ref "U2") (pin "9") (pinfunction "GND_9") (pintype "open_collector"))
      (node (ref "U3") (pin "10") (pinfunction "INPB_10") (pintype "open_collector"))
      (node (ref "U3") (pin "14") (pinfunction "XI_14") (pintype "open_collector"))
      (node (ref "U3") (pin "5") (pinfunction "AGND_5") (pintype "open_collector"))
      (node (ref "U3") (pin "9") (pinfunction "INNB_9") (pintype "open_collector"))
      (node (ref "U4") (pin "4") (pinfunction "GND_4") (pintype "open_collector"))
      (node (ref "U6") (pin "3") (pinfunction "GND_3") (pintype "open_collector"))
      (node (ref "U7") (pin "4") (pinfunction "GND_4") (pintype "open_collector"))
      (node (ref "U9") (pin "3") (pinfunction "GND_3") (pintype "open_collector"))
      (node (ref "U9") (pin "4") (pinfunction "GND_4") (pintype "open_collector"))
    )
    (net (code "34") (name "Net-(LED1-DOUT)") (class "Default")
      (node (ref "LED1") (pin "3") (pinfunction "DOUT_3") (pintype "open_collector"))
      (node (ref "LED2") (pin "1") (pinfunction "DIN_1") (pintype "open_collector"))
    )
    (net (code "35") (name "Net-(LED2-DOUT)") (class "Default")
      (node (ref "LED2") (pin "3") (pinfunction "DOUT_3") (pintype "open_collector"))
      (node (ref "LED3") (pin "1") (pinfunction "DIN_1") (pintype "open_collector"))
    )
    (net (code "36") (name "Net-(LED3-DOUT)") (class "Default")
      (node (ref "LED3") (pin "3") (pinfunction "DOUT_3") (pintype "open_collector"))
      (node (ref "LED4") (pin "1") (pinfunction "DIN_1") (pintype "open_collector"))
    )
    (net (code "37") (name "Net-(LED4-DOUT)") (class "Default")
      (node (ref "LED4") (pin "3") (pinfunction "DOUT_3") (pintype "open_collector"))
      (node (ref "LED5") (pin "1") (pinfunction "DIN_1") (pintype "open_collector"))
    )
    (net (code "38") (name "Net-(LED5-DOUT)") (class "Default")
      (node (ref "LED5") (pin "3") (pinfunction "DOUT_3") (pintype "open_collector"))
      (node (ref "LED6") (pin "1") (pinfunction "DIN_1") (pintype "open_collector"))
    )
    (net (code "39") (name "Net-(LED6-DOUT)") (class "Default")
      (node (ref "LED6") (pin "3") (pinfunction "DOUT_3") (pintype "open_collector"))
      (node (ref "LED7") (pin "1") (pinfunction "DIN_1") (pintype "open_collector"))
    )
    (net (code "40") (name "Net-(LED7-DOUT)") (class "Default")
      (node (ref "LED7") (pin "3") (pinfunction "DOUT_3") (pintype "open_collector"))
      (node (ref "LED8") (pin "1") (pinfunction "DIN_1") (pintype "open_collector"))
    )
    (net (code "41") (name "Net-(Q0-B)") (class "Default")
      (node (ref "Q0") (pin "2") (pinfunction "B_2") (pintype "passive"))
      (node (ref "U3") (pin "2") (pinfunction "BASE_2") (pintype "open_collector"))
    )
    (net (code "42") (name "Net-(Q0-C)") (class "Default")
      (node (ref "L0") (pin "2") (pinfunction "2_2") (pintype "passive"))
      (node (ref "Q0") (pin "3") (pinfunction "C_3") (pintype "passive"))
      (node (ref "R6") (pin "1") (pinfunction "1_1") (pintype "passive"))
      (node (ref "U3") (pin "3") (pinfunction "AVDD_3") (pintype "open_collector"))
    )
    (net (code "43") (name "Net-(U1-RST)") (class "Default")
      (node (ref "C25") (pin "2") (pinfunction "2_2") (pintype "passive"))
      (node (ref "R19") (pin "2") (pinfunction "2_2") (pintype "passive"))
      (node (ref "U1") (pin "9") (pinfunction "RST_9") (pintype "open_collector"))
    )
    (net (code "44") (name "Net-(U1-XTAL1)") (class "Default")
      (node (ref "C23") (pin "2") (pinfunction "2_2") (pintype "passive"))
      (node (ref "U1") (pin "19") (pinfunction "XTAL1_19") (pintype "open_collector"))
      (node (ref "X1") (pin "1") (pinfunction "1_1") (pintype "passive"))
    )
    (net (code "45") (name "Net-(U1-XTAL2)") (class "Default")
      (node (ref "C22") (pin "2") (pinfunction "2_2") (pintype "passive"))
      (node (ref "U1") (pin "18") (pinfunction "XTAL2_18") (pintype "open_collector"))
      (node (ref "X1") (pin "2") (pinfunction "2_2") (pintype "passive"))
    )
    (net (code "46") (name "Net-(U2-1.8VOUT)") (class "Default")
      (node (ref "C0") (pin "2") (pinfunction "2_2") (pintype "passive"))
      (node (ref "U2") (pin "13") (pinfunction "1.8VOUT_13") (pintype "open_collector"))
    )
    (net (code "47") (name "Net-(U2-VCP)") (class "Default")
      (node (ref "C1") (pin "2") (pinfunction "2_2") (pintype "passive"))
      (node (ref "U2") (pin "2") (pinfunction "VCP_2") (pintype "open_collector"))
    )
    (net (code "48") (name "Net-(U3-INNA)") (class "Default")
      (node (ref "C6") (pin "1") (pinfunction "1_1") (pintype "passive"))
      (node (ref "R4") (pin "1") (pinfunction "1_1") (pintype "passive"))
      (node (ref "U3") (pin "7") (pinfunction "INNA_7") (pintype "open_collector"))
    )
    (net (code "49") (name "Net-(U3-INPA)") (class "Default")
      (node (ref "C6") (pin "2") (pinfunction "2_2") (pintype "passive"))
      (node (ref "R3") (pin "1") (pinfunction "1_1") (pintype "passive"))
      (node (ref "U3") (pin "8") (pinfunction "INPA_8") (pintype "open_collector"))
    )
    (net (code "50") (name "Net-(U3-VBG)") (class "Default")
      (node (ref "C11") (pin "2") (pinfunction "2_2") (pintype "passive"))
      (node (ref "U3") (pin "6") (pinfunction "VBG_6") (pintype "open_collector"))
    )
    (net (code "51") (name "Net-(U3-VFB)") (class "Default")
      (node (ref "R5") (pin "1") (pinfunction "1_1") (pintype "passive"))
      (node (ref "R6") (pin "2") (pinfunction "2_2") (pintype "passive"))
      (node (ref "U3") (pin "4") (pinfunction "VFB_4") (pintype "open_collector"))
    )
    (net (code "52") (name "Net-(U7-VCC)") (class "Default")
      (node (ref "S1") (pin "4") (pinfunction "4_4") (pintype "open_collector"))
      (node (ref "U7") (pin "1") (pinfunction "VCC_1") (pintype "open_collector"))
    )
    (net (code "53") (name "unconnected-(LED8-DOUT-Pad3)") (class "Default")
      (node (ref "LED8") (pin "3") (pinfunction "DOUT_3") (pintype "open_collector+no_connect"))
    )
    (net (code "54") (name "unconnected-(P1-Pad1)") (class "Default")
      (node (ref "P1") (pin "1") (pinfunction "1_1") (pintype "open_collector"))
    )
    (net (code "55") (name "unconnected-(P1-Pad2)") (class "Default")
      (node (ref "P1") (pin "2") (pinfunction "2_2") (pintype "open_collector"))
    )
    (net (code "56") (name "unconnected-(P1-Pad3)") (class "Default")
      (node (ref "P1") (pin "3") (pinfunction "3_3") (pintype "open_collector"))
    )
    (net (code "57") (name "unconnected-(P1-Pad4)") (class "Default")
      (node (ref "P1") (pin "4") (pinfunction "4_4") (pintype "open_collector"))
    )
    (net (code "58") (name "unconnected-(P2-Pad1)") (class "Default")
      (node (ref "P2") (pin "1") (pinfunction "1_1") (pintype "open_collector"))
    )
    (net (code "59") (name "unconnected-(P2-Pad2)") (class "Default")
      (node (ref "P2") (pin "2") (pinfunction "2_2") (pintype "open_collector"))
    )
    (net (code "60") (name "unconnected-(P2-Pad3)") (class "Default")
      (node (ref "P2") (pin "3") (pinfunction "3_3") (pintype "open_collector"))
    )
    (net (code "61") (name "unconnected-(P2-Pad4)") (class "Default")
      (node (ref "P2") (pin "4") (pinfunction "4_4") (pintype "open_collector"))
    )
    (net (code "62") (name "unconnected-(P3-Pad1)") (class "Default")
      (node (ref "P3") (pin "1") (pinfunction "1_1") (pintype "open_collector"))
    )
    (net (code "63") (name "unconnected-(P3-Pad2)") (class "Default")
      (node (ref "P3") (pin "2") (pinfunction "2_2") (pintype "open_collector"))
    )
    (net (code "64") (name "unconnected-(P3-Pad3)") (class "Default")
      (node (ref "P3") (pin "3") (pinfunction "3_3") (pintype "open_collector"))
    )
    (net (code "65") (name "unconnected-(P3-Pad4)") (class "Default")
      (node (ref "P3") (pin "4") (pinfunction "4_4") (pintype "open_collector"))
    )
    (net (code "66") (name "unconnected-(P4-Pad1)") (class "Default")
      (node (ref "P4") (pin "1") (pinfunction "1_1") (pintype "open_collector"))
    )
    (net (code "67") (name "unconnected-(P4-Pad2)") (class "Default")
      (node (ref "P4") (pin "2") (pinfunction "2_2") (pintype "open_collector"))
    )
    (net (code "68") (name "unconnected-(P4-Pad3)") (class "Default")
      (node (ref "P4") (pin "3") (pinfunction "3_3") (pintype "open_collector"))
    )
    (net (code "69") (name "unconnected-(P4-Pad4)") (class "Default")
      (node (ref "P4") (pin "4") (pinfunction "4_4") (pintype "open_collector"))
    )
    (net (code "70") (name "unconnected-(P5-Pad1)") (class "Default")
      (node (ref "P5") (pin "1") (pinfunction "1_1") (pintype "open_collector"))
    )
    (net (code "71") (name "unconnected-(P5-Pad2)") (class "Default")
      (node (ref "P5") (pin "2") (pinfunction "2_2") (pintype "open_collector"))
    )
    (net (code "72") (name "unconnected-(P5-Pad3)") (class "Default")
      (node (ref "P5") (pin "3") (pinfunction "3_3") (pintype "open_collector"))
    )
    (net (code "73") (name "unconnected-(P5-Pad4)") (class "Default")
      (node (ref "P5") (pin "4") (pinfunction "4_4") (pintype "open_collector"))
    )
    (net (code "74") (name "unconnected-(P6-Pad1)") (class "Default")
      (node (ref "P6") (pin "1") (pinfunction "1_1") (pintype "open_collector"))
    )
    (net (code "75") (name "unconnected-(P6-Pad2)") (class "Default")
      (node (ref "P6") (pin "2") (pinfunction "2_2") (pintype "open_collector"))
    )
    (net (code "76") (name "unconnected-(P6-Pad3)") (class "Default")
      (node (ref "P6") (pin "3") (pinfunction "3_3") (pintype "open_collector"))
    )
    (net (code "77") (name "unconnected-(P6-Pad4)") (class "Default")
      (node (ref "P6") (pin "4") (pinfunction "4_4") (pintype "open_collector"))
    )
    (net (code "78") (name "unconnected-(P7-Pad1)") (class "Default")
      (node (ref "P7") (pin "1") (pinfunction "1_1") (pintype "open_collector"))
    )
    (net (code "79") (name "unconnected-(P7-Pad2)") (class "Default")
      (node (ref "P7") (pin "2") (pinfunction "2_2") (pintype "open_collector"))
    )
    (net (code "80") (name "unconnected-(P7-Pad3)") (class "Default")
      (node (ref "P7") (pin "3") (pinfunction "3_3") (pintype "open_collector"))
    )
    (net (code "81") (name "unconnected-(P7-Pad4)") (class "Default")
      (node (ref "P7") (pin "4") (pinfunction "4_4") (pintype "open_collector"))
    )
    (net (code "82") (name "unconnected-(P8-Pad1)") (class "Default")
      (node (ref "P8") (pin "1") (pinfunction "1_1") (pintype "open_collector"))
    )
    (net (code "83") (name "unconnected-(P8-Pad2)") (class "Default")
      (node (ref "P8") (pin "2") (pinfunction "2_2") (pintype "open_collector"))
    )
    (net (code "84") (name "unconnected-(P8-Pad3)") (class "Default")
      (node (ref "P8") (pin "3") (pinfunction "3_3") (pintype "open_collector"))
    )
    (net (code "85") (name "unconnected-(P8-Pad4)") (class "Default")
      (node (ref "P8") (pin "4") (pinfunction "4_4") (pintype "open_collector"))
    )
    (net (code "86") (name "unconnected-(P9-Pad1)") (class "Default")
      (node (ref "P9") (pin "1") (pinfunction "1_1") (pintype "open_collector"))
    )
    (net (code "87") (name "unconnected-(P9-Pad2)") (class "Default")
      (node (ref "P9") (pin "2") (pinfunction "2_2") (pintype "open_collector"))
    )
    (net (code "88") (name "unconnected-(P9-Pad3)") (class "Default")
      (node (ref "P9") (pin "3") (pinfunction "3_3") (pintype "open_collector"))
    )
    (net (code "89") (name "unconnected-(P9-Pad4)") (class "Default")
      (node (ref "P9") (pin "4") (pinfunction "4_4") (pintype "open_collector"))
    )
    (net (code "90") (name "unconnected-(P10-Pad1)") (class "Default")
      (node (ref "P10") (pin "1") (pinfunction "1_1") (pintype "open_collector"))
    )
    (net (code "91") (name "unconnected-(P10-Pad2)") (class "Default")
      (node (ref "P10") (pin "2") (pinfunction "2_2") (pintype "open_collector"))
    )
    (net (code "92") (name "unconnected-(P10-Pad3)") (class "Default")
      (node (ref "P10") (pin "3") (pinfunction "3_3") (pintype "open_collector"))
    )
    (net (code "93") (name "unconnected-(P10-Pad4)") (class "Default")
      (node (ref "P10") (pin "4") (pinfunction "4_4") (pintype "open_collector"))
    )
    (net (code "94") (name "unconnected-(P11-Pad1)") (class "Default")
      (node (ref "P11") (pin "1") (pinfunction "1_1") (pintype "open_collector"))
    )
    (net (code "95") (name "unconnected-(P11-Pad2)") (class "Default")
      (node (ref "P11") (pin "2") (pinfunction "2_2") (pintype "open_collector"))
    )
    (net (code "96") (name "unconnected-(P11-Pad3)") (class "Default")
      (node (ref "P11") (pin "3") (pinfunction "3_3") (pintype "open_collector"))
    )
    (net (code "97") (name "unconnected-(P11-Pad4)") (class "Default")
      (node (ref "P11") (pin "4") (pinfunction "4_4") (pintype "open_collector"))
    )
    (net (code "98") (name "unconnected-(P12-Pad1)") (class "Default")
      (node (ref "P12") (pin "1") (pinfunction "1_1") (pintype "open_collector"))
    )
    (net (code "99") (name "unconnected-(P12-Pad2)") (class "Default")
      (node (ref "P12") (pin "2") (pinfunction "2_2") (pintype "open_collector"))
    )
    (net (code "100") (name "unconnected-(P12-Pad3)") (class "Default")
      (node (ref "P12") (pin "3") (pinfunction "3_3") (pintype "open_collector"))
    )
    (net (code "101") (name "unconnected-(P12-Pad4)") (class "Default")
      (node (ref "P12") (pin "4") (pinfunction "4_4") (pintype "open_collector"))
    )
    (net (code "102") (name "unconnected-(P13-Pad1)") (class "Default")
      (node (ref "P13") (pin "1") (pinfunction "1_1") (pintype "open_collector"))
    )
    (net (code "103") (name "unconnected-(P13-Pad2)") (class "Default")
      (node (ref "P13") (pin "2") (pinfunction "2_2") (pintype "open_collector"))
    )
    (net (code "104") (name "unconnected-(P13-Pad3)") (class "Default")
      (node (ref "P13") (pin "3") (pinfunction "3_3") (pintype "open_collector"))
    )
    (net (code "105") (name "unconnected-(P13-Pad4)") (class "Default")
      (node (ref "P13") (pin "4") (pinfunction "4_4") (pintype "open_collector"))
    )
    (net (code "106") (name "unconnected-(P14-Pad1)") (class "Default")
      (node (ref "P14") (pin "1") (pinfunction "1_1") (pintype "open_collector"))
    )
    (net (code "107") (name "unconnected-(P14-Pad2)") (class "Default")
      (node (ref "P14") (pin "2") (pinfunction "2_2") (pintype "open_collector"))
    )
    (net (code "108") (name "unconnected-(P14-Pad3)") (class "Default")
      (node (ref "P14") (pin "3") (pinfunction "3_3") (pintype "open_collector"))
    )
    (net (code "109") (name "unconnected-(P14-Pad4)") (class "Default")
      (node (ref "P14") (pin "4") (pinfunction "4_4") (pintype "open_collector"))
    )
    (net (code "110") (name "unconnected-(P15-Pad1)") (class "Default")
      (node (ref "P15") (pin "1") (pinfunction "1_1") (pintype "open_collector"))
    )
    (net (code "111") (name "unconnected-(P15-Pad2)") (class "Default")
      (node (ref "P15") (pin "2") (pinfunction "2_2") (pintype "open_collector"))
    )
    (net (code "112") (name "unconnected-(P15-Pad3)") (class "Default")
      (node (ref "P15") (pin "3") (pinfunction "3_3") (pintype "open_collector"))
    )
    (net (code "113") (name "unconnected-(P15-Pad4)") (class "Default")
      (node (ref "P15") (pin "4") (pinfunction "4_4") (pintype "open_collector"))
    )
    (net (code "114") (name "unconnected-(P16-Pad1)") (class "Default")
      (node (ref "P16") (pin "1") (pinfunction "1_1") (pintype "open_collector"))
    )
    (net (code "115") (name "unconnected-(P16-Pad2)") (class "Default")
      (node (ref "P16") (pin "2") (pinfunction "2_2") (pintype "open_collector"))
    )
    (net (code "116") (name "unconnected-(P16-Pad3)") (class "Default")
      (node (ref "P16") (pin "3") (pinfunction "3_3") (pintype "open_collector"))
    )
    (net (code "117") (name "unconnected-(P16-Pad4)") (class "Default")
      (node (ref "P16") (pin "4") (pinfunction "4_4") (pintype "open_collector"))
    )
    (net (code "118") (name "unconnected-(P17-Pad1)") (class "Default")
      (node (ref "P17") (pin "1") (pinfunction "1_1") (pintype "open_collector"))
    )
    (net (code "119") (name "unconnected-(P17-Pad2)") (class "Default")
      (node (ref "P17") (pin "2") (pinfunction "2_2") (pintype "open_collector"))
    )
    (net (code "120") (name "unconnected-(P17-Pad3)") (class "Default")
      (node (ref "P17") (pin "3") (pinfunction "3_3") (pintype "open_collector"))
    )
    (net (code "121") (name "unconnected-(P17-Pad4)") (class "Default")
      (node (ref "P17") (pin "4") (pinfunction "4_4") (pintype "open_collector"))
    )
    (net (code "122") (name "unconnected-(P18-Pad1)") (class "Default")
      (node (ref "P18") (pin "1") (pinfunction "1_1") (pintype "open_collector"))
    )
    (net (code "123") (name "unconnected-(P18-Pad2)") (class "Default")
      (node (ref "P18") (pin "2") (pinfunction "2_2") (pintype "open_collector"))
    )
    (net (code "124") (name "unconnected-(P18-Pad3)") (class "Default")
      (node (ref "P18") (pin "3") (pinfunction "3_3") (pintype "open_collector"))
    )
    (net (code "125") (name "unconnected-(P18-Pad4)") (class "Default")
      (node (ref "P18") (pin "4") (pinfunction "4_4") (pintype "open_collector"))
    )
    (net (code "126") (name "unconnected-(P19-Pad1)") (class "Default")
      (node (ref "P19") (pin "1") (pinfunction "1_1") (pintype "open_collector"))
    )
    (net (code "127") (name "unconnected-(P19-Pad2)") (class "Default")
      (node (ref "P19") (pin "2") (pinfunction "2_2") (pintype "open_collector"))
    )
    (net (code "128") (name "unconnected-(P19-Pad3)") (class "Default")
      (node (ref "P19") (pin "3") (pinfunction "3_3") (pintype "open_collector"))
    )
    (net (code "129") (name "unconnected-(P19-Pad4)") (class "Default")
      (node (ref "P19") (pin "4") (pinfunction "4_4") (pintype "open_collector"))
    )
    (net (code "130") (name "unconnected-(P20-Pad1)") (class "Default")
      (node (ref "P20") (pin "1") (pinfunction "1_1") (pintype "open_collector"))
    )
    (net (code "131") (name "unconnected-(P20-Pad2)") (class "Default")
      (node (ref "P20") (pin "2") (pinfunction "2_2") (pintype "open_collector"))
    )
    (net (code "132") (name "unconnected-(P20-Pad3)") (class "Default")
      (node (ref "P20") (pin "3") (pinfunction "3_3") (pintype "open_collector"))
    )
    (net (code "133") (name "unconnected-(P20-Pad4)") (class "Default")
      (node (ref "P20") (pin "4") (pinfunction "4_4") (pintype "open_collector"))
    )
    (net (code "134") (name "unconnected-(P21-Pad1)") (class "Default")
      (node (ref "P21") (pin "1") (pinfunction "1_1") (pintype "open_collector"))
    )
    (net (code "135") (name "unconnected-(P21-Pad2)") (class "Default")
      (node (ref "P21") (pin "2") (pinfunction "2_2") (pintype "open_collector"))
    )
    (net (code "136") (name "unconnected-(P21-Pad3)") (class "Default")
      (node (ref "P21") (pin "3") (pinfunction "3_3") (pintype "open_collector"))
    )
    (net (code "137") (name "unconnected-(P21-Pad4)") (class "Default")
      (node (ref "P21") (pin "4") (pinfunction "4_4") (pintype "open_collector"))
    )
    (net (code "138") (name "unconnected-(S1-Pad1)") (class "Default")
      (node (ref "S1") (pin "1") (pinfunction "1_1") (pintype "open_collector+no_connect"))
    )
    (net (code "139") (name "unconnected-(S1-Pad2)") (class "Default")
      (node (ref "S1") (pin "2") (pinfunction "2_2") (pintype "open_collector+no_connect"))
    )
    (net (code "140") (name "unconnected-(S1-Pad3)") (class "Default")
      (node (ref "S1") (pin "3") (pinfunction "3_3") (pintype "open_collector+no_connect"))
    )
    (net (code "141") (name "unconnected-(S1-Pad6)") (class "Default")
      (node (ref "S1") (pin "6") (pinfunction "6_6") (pintype "open_collector+no_connect"))
    )
    (net (code "142") (name "unconnected-(U1-ALE{slash}P4.5-Pad30)") (class "Default")
      (node (ref "U1") (pin "30") (pinfunction "ALE/P4.5_30") (pintype "open_collector"))
    )
    (net (code "143") (name "unconnected-(U1-P0.7-Pad32)") (class "Default")
      (node (ref "U1") (pin "32") (pinfunction "P0.7_32") (pintype "open_collector"))
    )
    (net (code "144") (name "unconnected-(U1-P2.6-Pad27)") (class "Default")
      (node (ref "U1") (pin "27") (pinfunction "P2.6_27") (pintype "open_collector"))
    )
    (net (code "145") (name "unconnected-(U1-P2.7-Pad28)") (class "Default")
      (node (ref "U1") (pin "28") (pinfunction "P2.7_28") (pintype "open_collector"))
    )
    (net (code "146") (name "unconnected-(U1-P4.4-Pad29)") (class "Default")
      (node (ref "U1") (pin "29") (pinfunction "P4.4_29") (pintype "open_collector"))
    )
    (net (code "147") (name "unconnected-(U1-P4.6-Pad31)") (class "Default")
      (node (ref "U1") (pin "31") (pinfunction "P4.6_31") (pintype "open_collector"))
    )
    (net (code "148") (name "unconnected-(U1-T0{slash}P3.4-Pad14)") (class "Default")
      (node (ref "U1") (pin "14") (pinfunction "T0/P3.4_14") (pintype "open_collector"))
    )
    (net (code "149") (name "unconnected-(U1-T1{slash}P3.5-Pad15)") (class "Default")
      (node (ref "U1") (pin "15") (pinfunction "T1/P3.5_15") (pintype "open_collector"))
    )
    (net (code "150") (name "unconnected-(U1-T2EX{slash}P1.1-Pad2)") (class "Default")
      (node (ref "U1") (pin "2") (pinfunction "T2EX/P1.1_2") (pintype "open_collector"))
    )
    (net (code "151") (name "unconnected-(U1-T2{slash}P1.0-Pad1)") (class "Default")
      (node (ref "U1") (pin "1") (pinfunction "T2/P1.0_1") (pintype "open_collector"))
    )
    (net (code "152") (name "unconnected-(U1-~{INT0}{slash}P3.2-Pad12)") (class "Default")
      (node (ref "U1") (pin "12") (pinfunction "~{INT0}/P3.2_12") (pintype "open_collector"))
    )
    (net (code "153") (name "unconnected-(U1-~{INT1}{slash}P3.3-Pad13)") (class "Default")
      (node (ref "U1") (pin "13") (pinfunction "~{INT1}/P3.3_13") (pintype "open_collector"))
    )
    (net (code "154") (name "unconnected-(U2-'-Pad19)") (class "Default")
      (node (ref "U2") (pin "19") (pinfunction "'_19") (pintype "open_collector+no_connect"))
    )
    (net (code "155") (name "unconnected-(U3-XO-Pad13)") (class "Default")
      (node (ref "U3") (pin "13") (pinfunction "XO_13") (pintype "open_collector+no_connect"))
    )
    (net (code "156") (name "unconnected-(U4-OUT-Pad3)") (class "Default")
      (node (ref "U4") (pin "3") (pinfunction "OUT_3") (pintype "open_collector+no_connect"))
    )
    (net (code "157") (name "unconnected-(U4-PUSH-Pad5)") (class "Default")
      (node (ref "U4") (pin "5") (pinfunction "PUSH_5") (pintype "open_collector+no_connect"))
    )
  )
)
